# design.net
KiCad netlist of a schematic drawn in Altium Designer
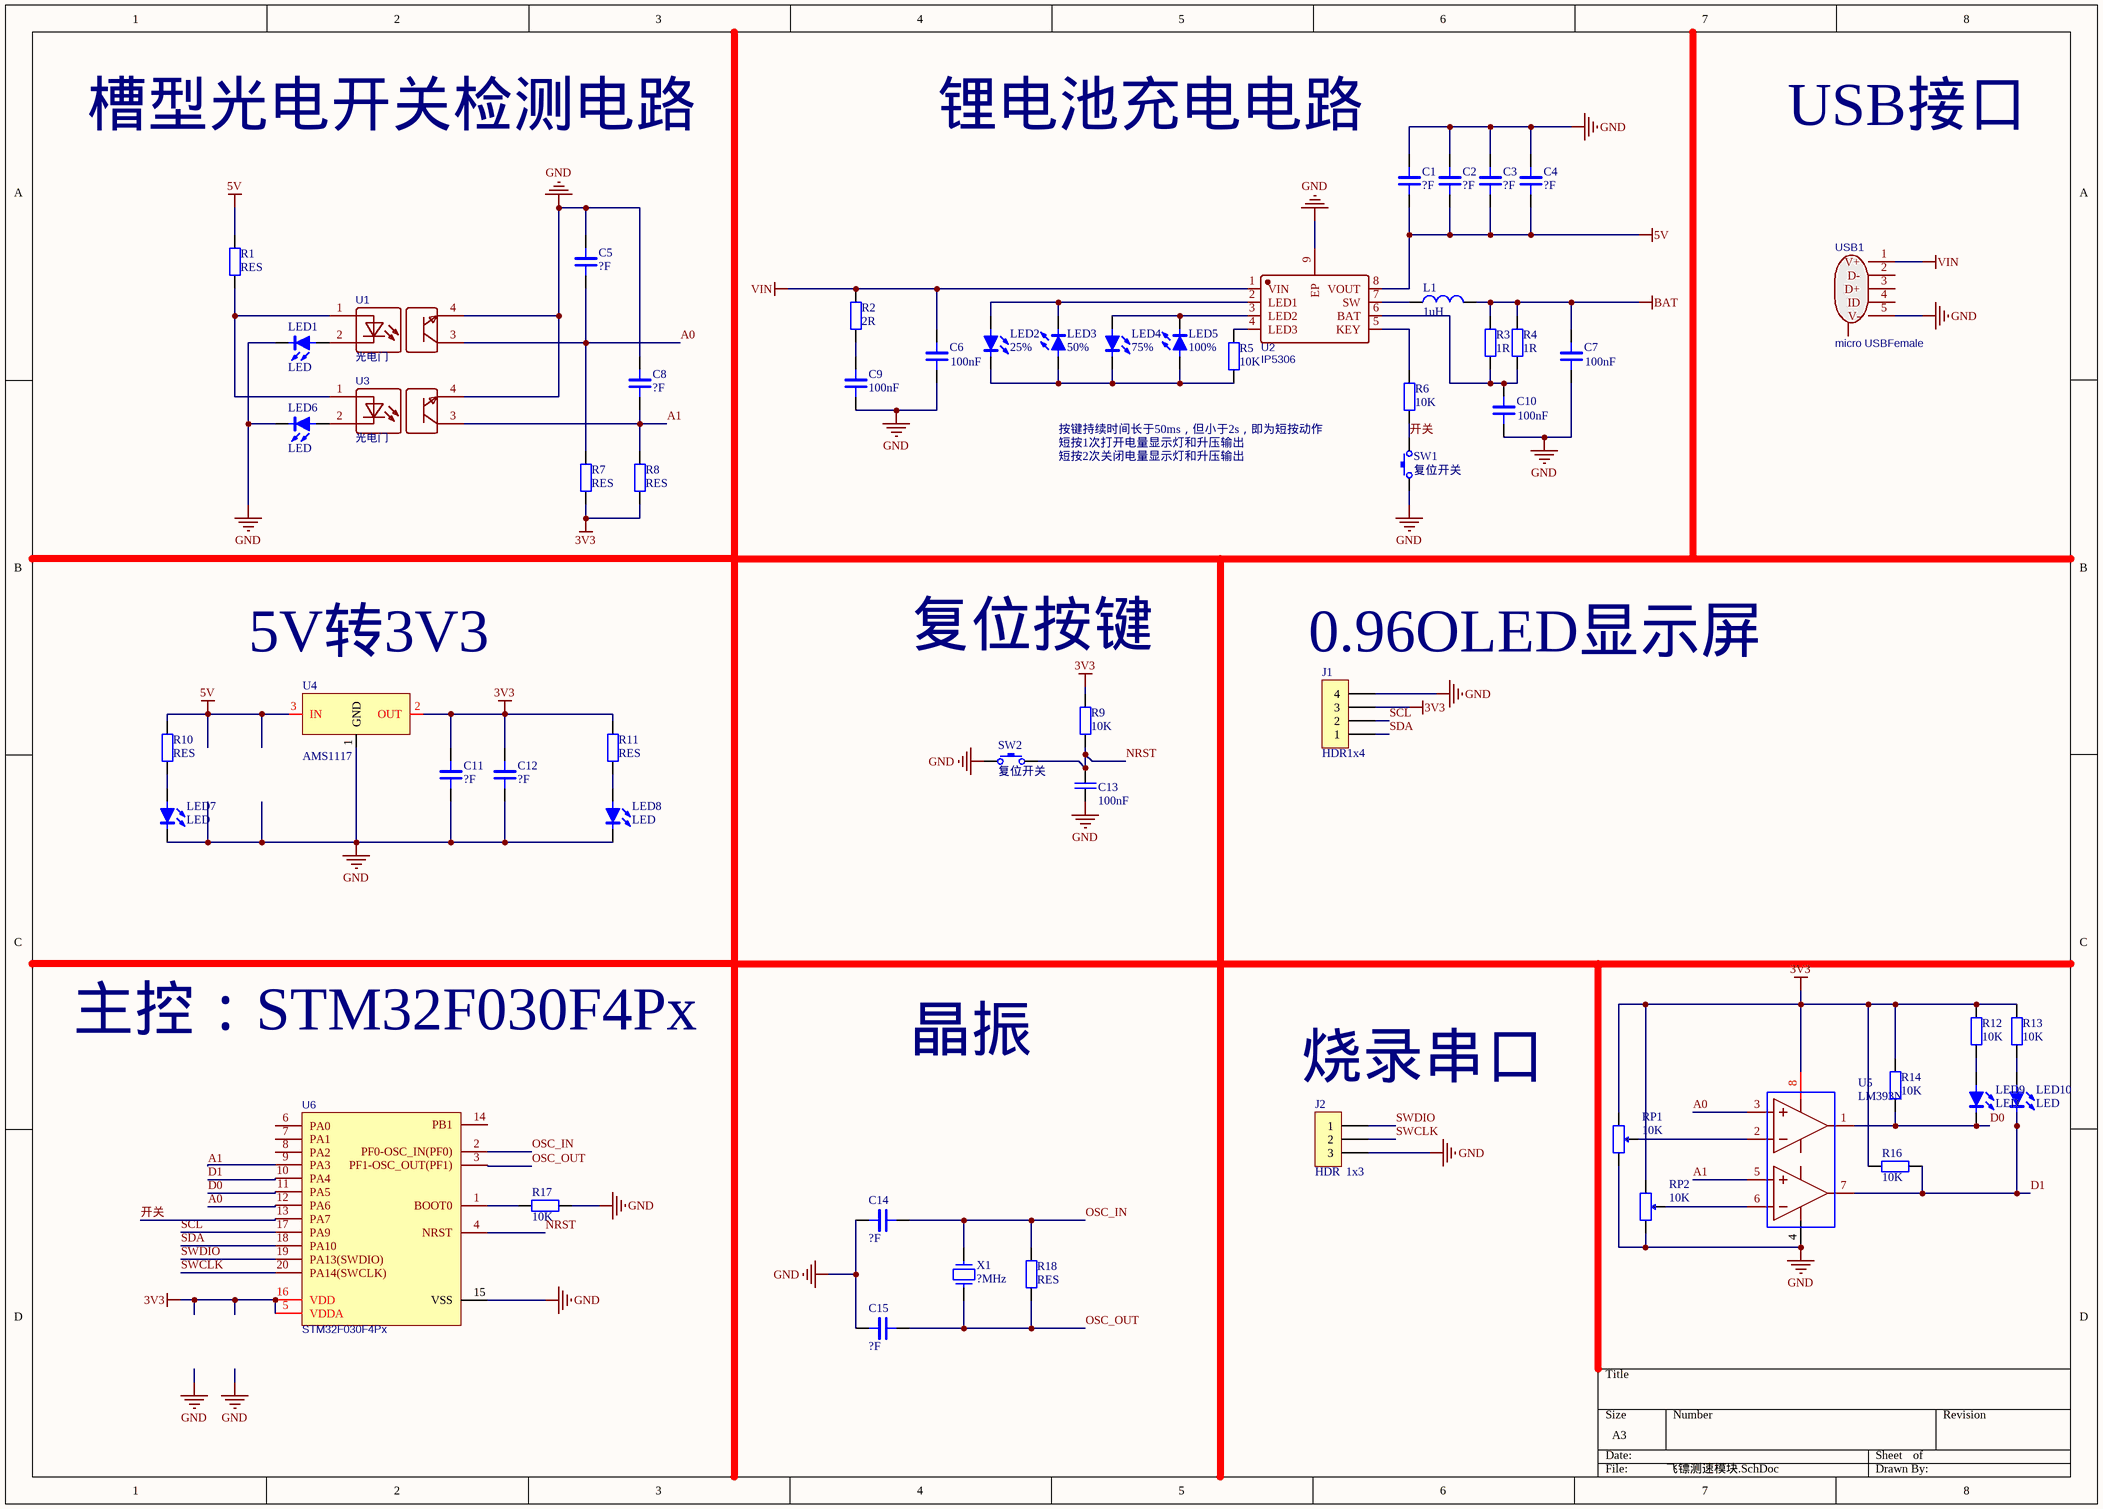
[diagram p0: 飞镖测速模块.SchDoc]

(export (version "E")
  (design (tool "Eeschema 10.0.6"))
  (components
    (comp (ref "C1")
      (value "?F")
      (footprint "1206_C")
      (description "Capacitor")
      (libsource (lib "General") (part "CAP"))
    )
    (comp (ref "C2")
      (value "?F")
      (footprint "1206_C")
      (description "Capacitor")
      (libsource (lib "General") (part "CAP"))
    )
    (comp (ref "C3")
      (value "?F")
      (footprint "1206_C")
      (description "Capacitor")
      (libsource (lib "General") (part "CAP"))
    )
    (comp (ref "C4")
      (value "?F")
      (footprint "1206_C")
      (description "Capacitor")
      (libsource (lib "General") (part "CAP"))
    )
    (comp (ref "C5")
      (value "?F")
      (footprint "0603_C")
      (description "Capacitor")
      (libsource (lib "General（旧）") (part "CAP"))
    )
    (comp (ref "C6")
      (value "100nF")
      (footprint "0603_C")
      (description "Capacitor")
      (libsource (lib "General") (part "CAP"))
    )
    (comp (ref "C7")
      (value "100nF")
      (footprint "0603_C")
      (description "Capacitor")
      (libsource (lib "General") (part "CAP"))
    )
    (comp (ref "C8")
      (value "?F")
      (footprint "0603_C")
      (description "Capacitor")
      (libsource (lib "General（旧）") (part "CAP"))
    )
    (comp (ref "C9")
      (value "100nF")
      (footprint "0603_C")
      (description "Capacitor")
      (libsource (lib "General") (part "CAP"))
    )
    (comp (ref "C10")
      (value "100nF")
      (footprint "0603_C")
      (description "Capacitor")
      (libsource (lib "General") (part "CAP"))
    )
    (comp (ref "C11")
      (value "?F")
      (footprint "1206_C")
      (description "Capacitor")
      (libsource (lib "General") (part "CAP"))
    )
    (comp (ref "C12")
      (value "?F")
      (footprint "1206_C")
      (description "Capacitor")
      (libsource (lib "General") (part "CAP"))
    )
    (comp (ref "C13")
      (value "100nF")
      (footprint "0603_C")
      (fields (field (name "PUBLISHER") "Altium Limited"))
      (libsource (lib "电容-电阻-电感") (part "Cap"))
    )
    (comp (ref "C14")
      (value "?F")
      (footprint "0603_C")
      (description "Capacitor")
      (libsource (lib "General（旧）") (part "CAP"))
    )
    (comp (ref "C15")
      (value "?F")
      (footprint "0603_C")
      (description "Capacitor")
      (libsource (lib "General（旧）") (part "CAP"))
    )
    (comp (ref "J1")
      (value "HDR1x4")
      (footprint "排针排母 4P 2.54mm")
      (description "Connector")
      (libsource (lib "General") (part "HDR1x4"))
    )
    (comp (ref "J2")
      (value "HDR  1x3")
      (footprint "排针排母 3P 2.54mm")
      (description "Connector")
      (libsource (lib "General（旧）") (part "HDR  1x3"))
    )
    (comp (ref "L1")
      (value "1uH")
      (footprint "SMD_4*4*3MM")
      (description "Inductor")
      (fields (field (name "PUBLISHER") "Altium Limited"))
      (libsource (lib "General") (part "Inductor"))
    )
    (comp (ref "LED1") (value "LED") (footprint "LED_0603") (libsource (lib "General（旧）") (part "LED")))
    (comp (ref "LED2")
      (value "25%")
      (footprint "LED_0603")
      (description "LED")
      (libsource (lib "General") (part "LED"))
    )
    (comp (ref "LED3")
      (value "50%")
      (footprint "LED_0603")
      (description "LED")
      (libsource (lib "General") (part "LED"))
    )
    (comp (ref "LED4")
      (value "75%")
      (footprint "LED_0603")
      (description "LED")
      (libsource (lib "General") (part "LED"))
    )
    (comp (ref "LED5")
      (value "100%")
      (footprint "LED_0603")
      (description "LED")
      (libsource (lib "General") (part "LED"))
    )
    (comp (ref "LED6") (value "LED") (footprint "LED_0603") (libsource (lib "General（旧）") (part "LED")))
    (comp (ref "LED7") (value "LED") (footprint "LED_0603") (libsource (lib "General（旧）") (part "LED")))
    (comp (ref "LED8") (value "LED") (footprint "LED_0603") (libsource (lib "General（旧）") (part "LED")))
    (comp (ref "LED9") (value "LED") (footprint "LED_0603") (libsource (lib "General（旧）") (part "LED")))
    (comp (ref "LED10") (value "LED") (footprint "LED_0603") (libsource (lib "General（旧）") (part "LED")))
    (comp (ref "R1")
      (value "RES")
      (footprint "0603_R")
      (description "Resistor")
      (libsource (lib "General") (part "RES"))
    )
    (comp (ref "R2")
      (value "2R")
      (footprint "0603_R")
      (description "Resistor")
      (libsource (lib "") (part "RES_1"))
    )
    (comp (ref "R3")
      (value "1R")
      (footprint "0603_R")
      (description "Resistor")
      (libsource (lib "") (part "RES_1"))
    )
    (comp (ref "R4")
      (value "1R")
      (footprint "0603_R")
      (description "Resistor")
      (libsource (lib "") (part "RES_1"))
    )
    (comp (ref "R5")
      (value "10K")
      (footprint "0603_R")
      (description "Resistor")
      (libsource (lib "") (part "RES_1"))
    )
    (comp (ref "R6")
      (value "10K")
      (footprint "0603_R")
      (description "Resistor")
      (libsource (lib "") (part "RES_1"))
    )
    (comp (ref "R7")
      (value "RES")
      (footprint "0603_R")
      (description "Resistor")
      (libsource (lib "General") (part "RES"))
    )
    (comp (ref "R8")
      (value "RES")
      (footprint "0603_R")
      (description "Resistor")
      (libsource (lib "General") (part "RES"))
    )
    (comp (ref "R9")
      (value "10K")
      (footprint "0603_R")
      (fields (field (name "PUBLISHER") "Altium Limited"))
      (libsource (lib "电容-电阻-电感") (part "Res"))
    )
    (comp (ref "R10")
      (value "RES")
      (footprint "0603_R")
      (description "Resistor")
      (libsource (lib "General（旧）") (part "RES"))
    )
    (comp (ref "R11")
      (value "RES")
      (footprint "0603_R")
      (description "Resistor")
      (libsource (lib "General（旧）") (part "RES"))
    )
    (comp (ref "R12")
      (value "10K")
      (footprint "0603_R")
      (fields (field (name "PUBLISHER") "Altium Limited"))
      (libsource (lib "") (part "Res_1"))
    )
    (comp (ref "R13")
      (value "10K")
      (footprint "0603_R")
      (fields (field (name "PUBLISHER") "Altium Limited"))
      (libsource (lib "") (part "Res_1"))
    )
    (comp (ref "R14")
      (value "10K")
      (footprint "0603_R")
      (fields (field (name "PUBLISHER") "Altium Limited"))
      (libsource (lib "电容-电阻-电感") (part "Res"))
    )
    (comp (ref "R16")
      (value "10K")
      (footprint "0603_R")
      (fields (field (name "PUBLISHER") "Altium Limited"))
      (libsource (lib "") (part "Res_2"))
    )
    (comp (ref "R17")
      (value "10K")
      (footprint "0603_R")
      (description "Resistor")
      (libsource (lib "") (part "RES_2"))
    )
    (comp (ref "R18")
      (value "RES")
      (footprint "0603_R")
      (description "Resistor")
      (libsource (lib "General（旧）") (part "RES"))
    )
    (comp (ref "RP1")
      (value "10K")
      (footprint "RM065")
      (description "插件单联电位器")
      (fields (field (name "版权归属") "源创客"))
      (libsource (lib "电阻-电容-电感") (part "RP-ID"))
    )
    (comp (ref "RP2")
      (value "10K")
      (footprint "RM065")
      (description "插件单联电位器")
      (fields (field (name "版权归属") "源创客"))
      (libsource (lib "电阻-电容-电感") (part "RP-ID"))
    )
    (comp (ref "SW1")
      (value "复位开关")
      (footprint "SW-按键")
      (description "开关")
      (libsource (lib "General") (part "复位开关"))
    )
    (comp (ref "SW2")
      (value "复位开关")
      (footprint "SW-按键")
      (description "开关")
      (libsource (lib "General") (part "复位开关"))
    )
    (comp (ref "U1")
      (value "光电门")
      (footprint "ZGY1150(ITR)")
      (fields
        (field (name "BOM_SUPPLIER PART") "C277764")
        (field (name "BOM_MANUFACTURER PART") "ZGY1150(ITR)")
        (field (name "CONTRIBUTOR") "LCSC")
      )
      (libsource (lib "General") (part "光电门"))
    )
    (comp (ref "U2")
      (value "IP5306")
      (footprint "SOP8-EP")
      (description "电池管理芯片")
      (fields (field (name "BOM_SUPPLIER PART") "C181692") (field (name "CONTRIBUTOR") "LCSC"))
      (libsource (lib "General") (part "IP5306"))
    )
    (comp (ref "U3")
      (value "光电门")
      (footprint "ZGY1150(ITR)")
      (fields
        (field (name "BOM_SUPPLIER PART") "C277764")
        (field (name "BOM_MANUFACTURER PART") "ZGY1150(ITR)")
        (field (name "CONTRIBUTOR") "LCSC")
      )
      (libsource (lib "General") (part "光电门"))
    )
    (comp (ref "U4")
      (value "AMS1117")
      (footprint "SOT-223")
      (description "LDO")
      (libsource (lib "General") (part "AMS1117"))
    )
    (comp (ref "U5")
      (value "LM393N")
      (footprint "SOP8")
      (description "电压比较器")
      (fields
        (field (name "BOM_SUPPLIER PART") "C431540")
        (field (name "BOM_MANUFACTURER PART") "MSK12C02")
        (field (name "CONTRIBUTOR") "LCSC")
      )
      (libsource (lib "General（旧）") (part "LM393N"))
    )
    (comp (ref "U6")
      (value "STM32F030F4Px")
      (footprint "TSSOP-20")
      (description "STM32单片机")
      (fields
        (field (name "BOM_MANUFACTURER PART") "STM32F030F4P6")
        (field (name "BOM_SUPPLIER PART") "C32908")
      )
      (libsource (lib "General") (part "STM32F030F4Px"))
    )
    (comp (ref "USB1")
      (value "micro USBFemale")
      (footprint "MICRO-USB-SMD_5P-P0.65-H-F_C10418")
      (fields (field (name "BOM_SUPPLIER PART") "C10418"))
      (libsource (lib "General（旧）") (part "micro USBFemale"))
    )
    (comp (ref "X1")
      (value "?MHz")
      (footprint "XTAL 直插")
      (description "8MHz,12MHz")
      (libsource (lib "General（旧）") (part "XTAL"))
    )
  )
  (nets
    (net (code "1") (name "/A0") (class "Default")
      (node (ref "C5") (pin "1") (pinfunction "1_1") (pintype "passive"))
      (node (ref "R7") (pin "1") (pinfunction "1_1") (pintype "passive"))
      (node (ref "U1") (pin "3") (pinfunction "3_3") (pintype "passive"))
      (node (ref "U5") (pin "3") (pinfunction "IN_A+_3") (pintype "passive"))
      (node (ref "U6") (pin "12") (pinfunction "PA6_12") (pintype "passive"))
    )
    (net (code "2") (name "/A1") (class "Default")
      (node (ref "C8") (pin "1") (pinfunction "1_1") (pintype "passive"))
      (node (ref "R8") (pin "1") (pinfunction "1_1") (pintype "passive"))
      (node (ref "U3") (pin "3") (pinfunction "3_3") (pintype "passive"))
      (node (ref "U5") (pin "5") (pinfunction "IN_B+_5") (pintype "passive"))
      (node (ref "U6") (pin "9") (pinfunction "PA3_9") (pintype "passive"))
    )
    (net (code "3") (name "/D0") (class "Default")
      (node (ref "LED9") (pin "2") (pinfunction "C_2") (pintype "passive"))
      (node (ref "R14") (pin "1") (pinfunction "1_1") (pintype "passive"))
      (node (ref "U5") (pin "1") (pinfunction "OUT_1") (pintype "passive"))
      (node (ref "U6") (pin "11") (pinfunction "PA5_11") (pintype "passive"))
    )
    (net (code "4") (name "/D1") (class "Default")
      (node (ref "LED10") (pin "2") (pinfunction "C_2") (pintype "passive"))
      (node (ref "R16") (pin "2") (pinfunction "2_2") (pintype "passive"))
      (node (ref "U5") (pin "7") (pinfunction "OUT_7") (pintype "passive"))
      (node (ref "U6") (pin "10") (pinfunction "PA4_10") (pintype "passive"))
    )
    (net (code "5") (name "/NRST") (class "Default")
      (node (ref "C13") (pin "1") (pinfunction "1_1") (pintype "passive"))
      (node (ref "R9") (pin "1") (pinfunction "1_1") (pintype "passive"))
      (node (ref "SW2") (pin "2") (pinfunction "2_2") (pintype "passive"))
      (node (ref "U6") (pin "4") (pinfunction "NRST_4") (pintype "passive"))
    )
    (net (code "6") (name "/OSC_IN") (class "Default")
      (node (ref "C14") (pin "1") (pinfunction "1_1") (pintype "passive"))
      (node (ref "R18") (pin "2") (pinfunction "2_2") (pintype "passive"))
      (node (ref "U6") (pin "2") (pinfunction "PF0-OSC_IN(PF0)_2") (pintype "passive"))
      (node (ref "X1") (pin "2") (pinfunction "2_2") (pintype "passive"))
    )
    (net (code "7") (name "/OSC_OUT") (class "Default")
      (node (ref "C15") (pin "1") (pinfunction "1_1") (pintype "passive"))
      (node (ref "R18") (pin "1") (pinfunction "1_1") (pintype "passive"))
      (node (ref "U6") (pin "3") (pinfunction "PF1-OSC_OUT(PF1)_3") (pintype "passive"))
      (node (ref "X1") (pin "1") (pinfunction "1_1") (pintype "passive"))
    )
    (net (code "8") (name "/SCL") (class "Default")
      (node (ref "J1") (pin "2") (pinfunction "2_2") (pintype "passive"))
      (node (ref "U6") (pin "17") (pinfunction "PA9_17") (pintype "passive"))
    )
    (net (code "9") (name "/SDA") (class "Default")
      (node (ref "J1") (pin "1") (pinfunction "1_1") (pintype "passive"))
      (node (ref "U6") (pin "18") (pinfunction "PA10_18") (pintype "passive"))
    )
    (net (code "10") (name "/SWCLK") (class "Default")
      (node (ref "J2") (pin "2") (pinfunction "2_2") (pintype "passive"))
      (node (ref "U6") (pin "20") (pinfunction "PA14(SWCLK)_20") (pintype "passive"))
    )
    (net (code "11") (name "/SWDIO") (class "Default")
      (node (ref "J2") (pin "1") (pinfunction "1_1") (pintype "passive"))
      (node (ref "U6") (pin "19") (pinfunction "PA13(SWDIO)_19") (pintype "passive"))
    )
    (net (code "12") (name "/开关") (class "Default")
      (node (ref "R6") (pin "1") (pinfunction "1_1") (pintype "passive"))
      (node (ref "SW1") (pin "2") (pinfunction "2_2") (pintype "passive"))
      (node (ref "U6") (pin "13") (pinfunction "PA7_13") (pintype "passive"))
    )
    (net (code "13") (name "3V3") (class "Default")
      (node (ref "C11") (pin "2") (pinfunction "2_2") (pintype "passive"))
      (node (ref "C12") (pin "2") (pinfunction "2_2") (pintype "passive"))
      (node (ref "J1") (pin "3") (pinfunction "3_3") (pintype "passive"))
      (node (ref "R11") (pin "2") (pinfunction "2_2") (pintype "passive"))
      (node (ref "R12") (pin "1") (pinfunction "1_1") (pintype "passive"))
      (node (ref "R13") (pin "1") (pinfunction "1_1") (pintype "passive"))
      (node (ref "R14") (pin "2") (pinfunction "2_2") (pintype "passive"))
      (node (ref "R16") (pin "1") (pinfunction "1_1") (pintype "passive"))
      (node (ref "R7") (pin "2") (pinfunction "2_2") (pintype "passive"))
      (node (ref "R8") (pin "2") (pinfunction "2_2") (pintype "passive"))
      (node (ref "R9") (pin "2") (pinfunction "2_2") (pintype "passive"))
      (node (ref "RP1") (pin "1") (pinfunction "1_1") (pintype "passive"))
      (node (ref "RP2") (pin "1") (pinfunction "1_1") (pintype "passive"))
      (node (ref "U4") (pin "2") (pinfunction "OUT_2") (pintype "passive"))
      (node (ref "U5") (pin "8") (pinfunction "V+_8") (pintype "passive"))
      (node (ref "U6") (pin "16") (pinfunction "VDD_16") (pintype "passive"))
      (node (ref "U6") (pin "5") (pinfunction "VDDA_5") (pintype "passive"))
    )
    (net (code "14") (name "5V") (class "Default")
      (node (ref "C1") (pin "1") (pinfunction "1_1") (pintype "passive"))
      (node (ref "C2") (pin "1") (pinfunction "1_1") (pintype "passive"))
      (node (ref "C3") (pin "1") (pinfunction "1_1") (pintype "passive"))
      (node (ref "C4") (pin "1") (pinfunction "1_1") (pintype "passive"))
      (node (ref "R1") (pin "1") (pinfunction "1_1") (pintype "passive"))
      (node (ref "R10") (pin "2") (pinfunction "2_2") (pintype "passive"))
      (node (ref "U2") (pin "8") (pinfunction "VOUT_8") (pintype "passive"))
      (node (ref "U4") (pin "3") (pinfunction "IN_3") (pintype "passive"))
    )
    (net (code "15") (name "BAT") (class "Default")
      (node (ref "C7") (pin "2") (pinfunction "2_2") (pintype "passive"))
      (node (ref "L1") (pin "2") (pinfunction "2_2") (pintype "passive"))
      (node (ref "R3") (pin "2") (pinfunction "2_2") (pintype "passive"))
      (node (ref "R4") (pin "2") (pinfunction "2_2") (pintype "passive"))
    )
    (net (code "16") (name "GND") (class "Default")
      (node (ref "C1") (pin "2") (pinfunction "2_2") (pintype "passive"))
      (node (ref "C10") (pin "1") (pinfunction "1_1") (pintype "passive"))
      (node (ref "C11") (pin "1") (pinfunction "1_1") (pintype "passive"))
      (node (ref "C12") (pin "1") (pinfunction "1_1") (pintype "passive"))
      (node (ref "C13") (pin "2") (pinfunction "2_2") (pintype "passive"))
      (node (ref "C14") (pin "2") (pinfunction "2_2") (pintype "passive"))
      (node (ref "C15") (pin "2") (pinfunction "2_2") (pintype "passive"))
      (node (ref "C2") (pin "2") (pinfunction "2_2") (pintype "passive"))
      (node (ref "C3") (pin "2") (pinfunction "2_2") (pintype "passive"))
      (node (ref "C4") (pin "2") (pinfunction "2_2") (pintype "passive"))
      (node (ref "C5") (pin "2") (pinfunction "2_2") (pintype "passive"))
      (node (ref "C6") (pin "1") (pinfunction "1_1") (pintype "passive"))
      (node (ref "C7") (pin "1") (pinfunction "1_1") (pintype "passive"))
      (node (ref "C8") (pin "2") (pinfunction "2_2") (pintype "passive"))
      (node (ref "C9") (pin "1") (pinfunction "1_1") (pintype "passive"))
      (node (ref "J1") (pin "4") (pinfunction "4_4") (pintype "passive"))
      (node (ref "J2") (pin "3") (pinfunction "3_3") (pintype "passive"))
      (node (ref "LED1") (pin "2") (pinfunction "C_2") (pintype "passive"))
      (node (ref "LED6") (pin "2") (pinfunction "C_2") (pintype "passive"))
      (node (ref "LED7") (pin "2") (pinfunction "C_2") (pintype "passive"))
      (node (ref "LED8") (pin "2") (pinfunction "C_2") (pintype "passive"))
      (node (ref "R17") (pin "2") (pinfunction "2_2") (pintype "passive"))
      (node (ref "RP1") (pin "3") (pinfunction "3_3") (pintype "passive"))
      (node (ref "RP2") (pin "3") (pinfunction "3_3") (pintype "passive"))
      (node (ref "SW1") (pin "1") (pinfunction "1_1") (pintype "passive"))
      (node (ref "SW2") (pin "1") (pinfunction "1_1") (pintype "passive"))
      (node (ref "U1") (pin "4") (pinfunction "4_4") (pintype "passive"))
      (node (ref "U2") (pin "9") (pinfunction "EP_9") (pintype "passive"))
      (node (ref "U3") (pin "4") (pinfunction "4_4") (pintype "passive"))
      (node (ref "U4") (pin "1") (pinfunction "GND_1") (pintype "passive"))
      (node (ref "U5") (pin "4") (pinfunction "V-_4") (pintype "passive"))
      (node (ref "U6") (pin "15") (pinfunction "VSS_15") (pintype "passive"))
      (node (ref "USB1") (pin "5") (pinfunction "V-_5") (pintype "passive"))
    )
    (net (code "17") (name "Net-(C9-Pad2)") (class "Default")
      (node (ref "C9") (pin "2") (pinfunction "2_2") (pintype "passive"))
      (node (ref "R2") (pin "1") (pinfunction "1_1") (pintype "passive"))
    )
    (net (code "18") (name "Net-(LED1-A)") (class "Default")
      (node (ref "LED1") (pin "1") (pinfunction "A_1") (pintype "passive"))
      (node (ref "U1") (pin "2") (pinfunction "2_2") (pintype "passive"))
    )
    (net (code "19") (name "Net-(LED2-A)") (class "Default")
      (node (ref "LED2") (pin "1") (pinfunction "A_1") (pintype "passive"))
      (node (ref "LED3") (pin "2") (pinfunction "C_2") (pintype "passive"))
      (node (ref "U2") (pin "2") (pinfunction "LED1_2") (pintype "passive"))
    )
    (net (code "20") (name "Net-(LED2-C)") (class "Default")
      (node (ref "LED2") (pin "2") (pinfunction "C_2") (pintype "passive"))
      (node (ref "LED3") (pin "1") (pinfunction "A_1") (pintype "passive"))
      (node (ref "LED4") (pin "2") (pinfunction "C_2") (pintype "passive"))
      (node (ref "LED5") (pin "1") (pinfunction "A_1") (pintype "passive"))
      (node (ref "R5") (pin "1") (pinfunction "1_1") (pintype "passive"))
    )
    (net (code "21") (name "Net-(LED4-A)") (class "Default")
      (node (ref "LED4") (pin "1") (pinfunction "A_1") (pintype "passive"))
      (node (ref "LED5") (pin "2") (pinfunction "C_2") (pintype "passive"))
      (node (ref "U2") (pin "3") (pinfunction "LED2_3") (pintype "passive"))
    )
    (net (code "22") (name "Net-(LED6-A)") (class "Default")
      (node (ref "LED6") (pin "1") (pinfunction "A_1") (pintype "passive"))
      (node (ref "U3") (pin "2") (pinfunction "2_2") (pintype "passive"))
    )
    (net (code "23") (name "Net-(LED7-A)") (class "Default")
      (node (ref "LED7") (pin "1") (pinfunction "A_1") (pintype "passive"))
      (node (ref "R10") (pin "1") (pinfunction "1_1") (pintype "passive"))
    )
    (net (code "24") (name "Net-(LED8-A)") (class "Default")
      (node (ref "LED8") (pin "1") (pinfunction "A_1") (pintype "passive"))
      (node (ref "R11") (pin "1") (pinfunction "1_1") (pintype "passive"))
    )
    (net (code "25") (name "Net-(LED9-A)") (class "Default")
      (node (ref "LED9") (pin "1") (pinfunction "A_1") (pintype "passive"))
      (node (ref "R12") (pin "2") (pinfunction "2_2") (pintype "passive"))
    )
    (net (code "26") (name "Net-(LED10-A)") (class "Default")
      (node (ref "LED10") (pin "1") (pinfunction "A_1") (pintype "passive"))
      (node (ref "R13") (pin "2") (pinfunction "2_2") (pintype "passive"))
    )
    (net (code "27") (name "Net-(R1-Pad2)") (class "Default")
      (node (ref "R1") (pin "2") (pinfunction "2_2") (pintype "passive"))
      (node (ref "U1") (pin "1") (pinfunction "1_1") (pintype "passive"))
      (node (ref "U3") (pin "1") (pinfunction "1_1") (pintype "passive"))
    )
    (net (code "28") (name "Net-(U2-BAT)") (class "Default")
      (node (ref "C10") (pin "2") (pinfunction "2_2") (pintype "passive"))
      (node (ref "R3") (pin "1") (pinfunction "1_1") (pintype "passive"))
      (node (ref "R4") (pin "1") (pinfunction "1_1") (pintype "passive"))
      (node (ref "U2") (pin "6") (pinfunction "BAT_6") (pintype "passive"))
    )
    (net (code "29") (name "Net-(U2-KEY)") (class "Default")
      (node (ref "R6") (pin "2") (pinfunction "2_2") (pintype "passive"))
      (node (ref "U2") (pin "5") (pinfunction "KEY_5") (pintype "passive"))
    )
    (net (code "30") (name "Net-(U2-LED3)") (class "Default")
      (node (ref "R5") (pin "2") (pinfunction "2_2") (pintype "passive"))
      (node (ref "U2") (pin "4") (pinfunction "LED3_4") (pintype "passive"))
    )
    (net (code "31") (name "Net-(U2-SW)") (class "Default")
      (node (ref "L1") (pin "1") (pinfunction "1_1") (pintype "passive"))
      (node (ref "U2") (pin "7") (pinfunction "SW_7") (pintype "passive"))
    )
    (net (code "32") (name "Net-(U5-IN_A-)") (class "Default")
      (node (ref "RP1") (pin "2") (pinfunction "2_2") (pintype "passive"))
      (node (ref "U5") (pin "2") (pinfunction "IN_A-_2") (pintype "passive"))
    )
    (net (code "33") (name "Net-(U5-IN_B-)") (class "Default")
      (node (ref "RP2") (pin "2") (pinfunction "2_2") (pintype "passive"))
      (node (ref "U5") (pin "6") (pinfunction "IN_B-_6") (pintype "passive"))
    )
    (net (code "34") (name "Net-(U6-BOOT0)") (class "Default")
      (node (ref "R17") (pin "1") (pinfunction "1_1") (pintype "passive"))
      (node (ref "U6") (pin "1") (pinfunction "BOOT0_1") (pintype "passive"))
    )
    (net (code "35") (name "VIN") (class "Default")
      (node (ref "C6") (pin "2") (pinfunction "2_2") (pintype "passive"))
      (node (ref "R2") (pin "2") (pinfunction "2_2") (pintype "passive"))
      (node (ref "U2") (pin "1") (pinfunction "VIN_1") (pintype "passive"))
      (node (ref "USB1") (pin "1") (pinfunction "V+_1") (pintype "passive"))
    )
    (net (code "36") (name "unconnected-(U6-PA0-Pad6)") (class "Default")
      (node (ref "U6") (pin "6") (pinfunction "PA0_6") (pintype "passive"))
    )
    (net (code "37") (name "unconnected-(U6-PA1-Pad7)") (class "Default")
      (node (ref "U6") (pin "7") (pinfunction "PA1_7") (pintype "passive"))
    )
    (net (code "38") (name "unconnected-(U6-PA2-Pad8)") (class "Default")
      (node (ref "U6") (pin "8") (pinfunction "PA2_8") (pintype "passive"))
    )
    (net (code "39") (name "unconnected-(U6-PB1-Pad14)") (class "Default")
      (node (ref "U6") (pin "14") (pinfunction "PB1_14") (pintype "passive"))
    )
    (net (code "40") (name "unconnected-(USB1-D+-Pad3)") (class "Default")
      (node (ref "USB1") (pin "3") (pinfunction "D+_3") (pintype "passive"))
    )
    (net (code "41") (name "unconnected-(USB1-D--Pad2)") (class "Default")
      (node (ref "USB1") (pin "2") (pinfunction "D-_2") (pintype "passive"))
    )
    (net (code "42") (name "unconnected-(USB1-ID-Pad4)") (class "Default")
      (node (ref "USB1") (pin "4") (pinfunction "ID_4") (pintype "passive"))
    )
    (net (code "43") (name "unconnected-(USB1-MTN-Pad0)") (class "Default")
      (node (ref "USB1") (pin "0") (pinfunction "MTN_0") (pintype "passive"))
    )
  )
)
